# O2_PROM_ISP_A00.net
KiCad netlist of a schematic drawn in EAGLE
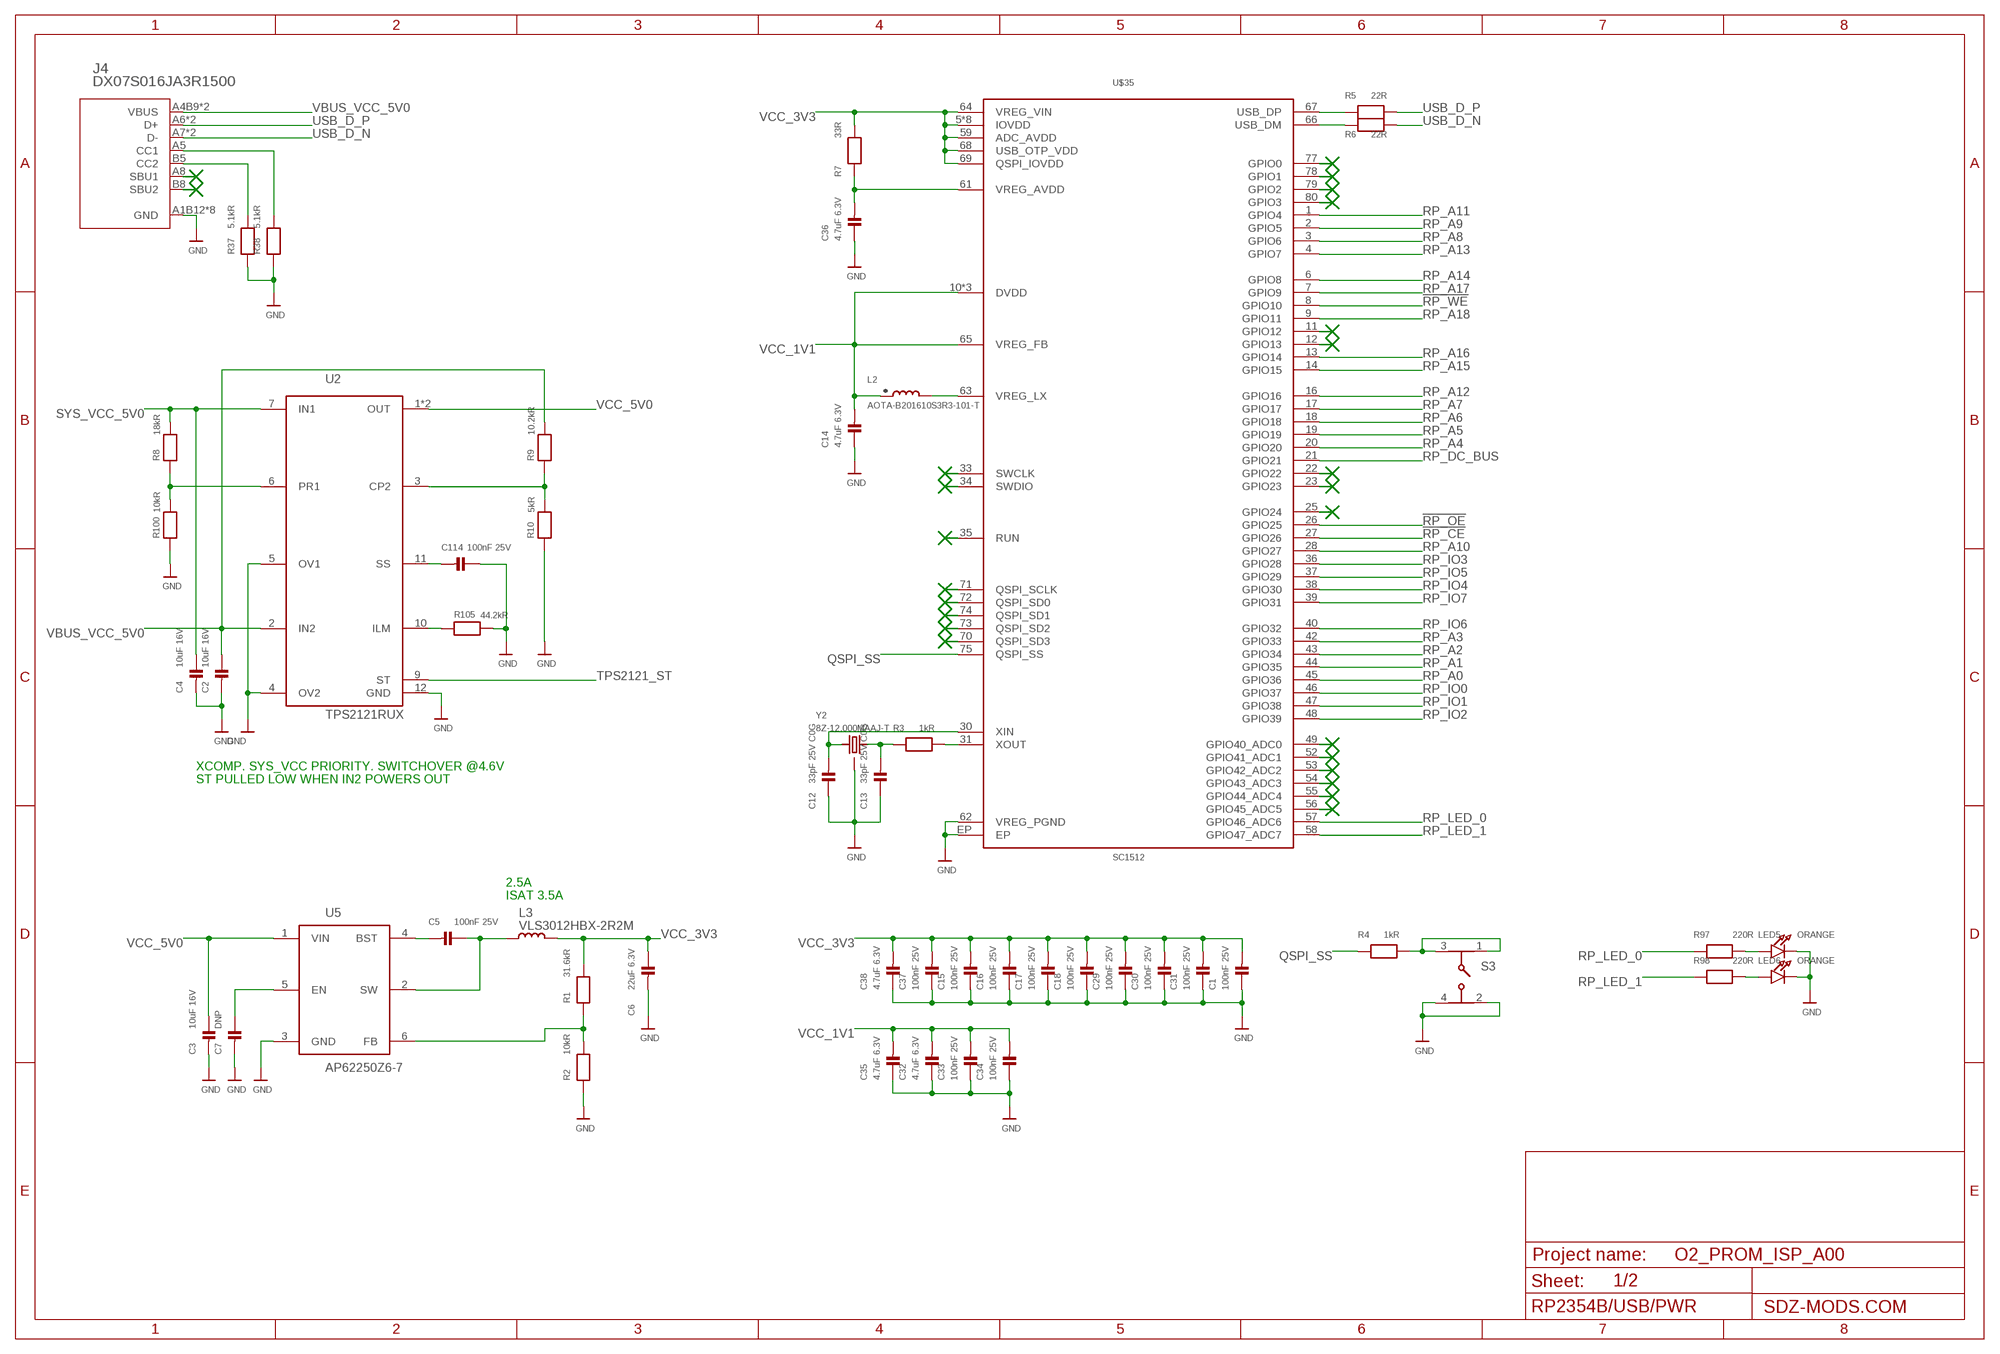
[diagram p0: schematic, sheet 1]
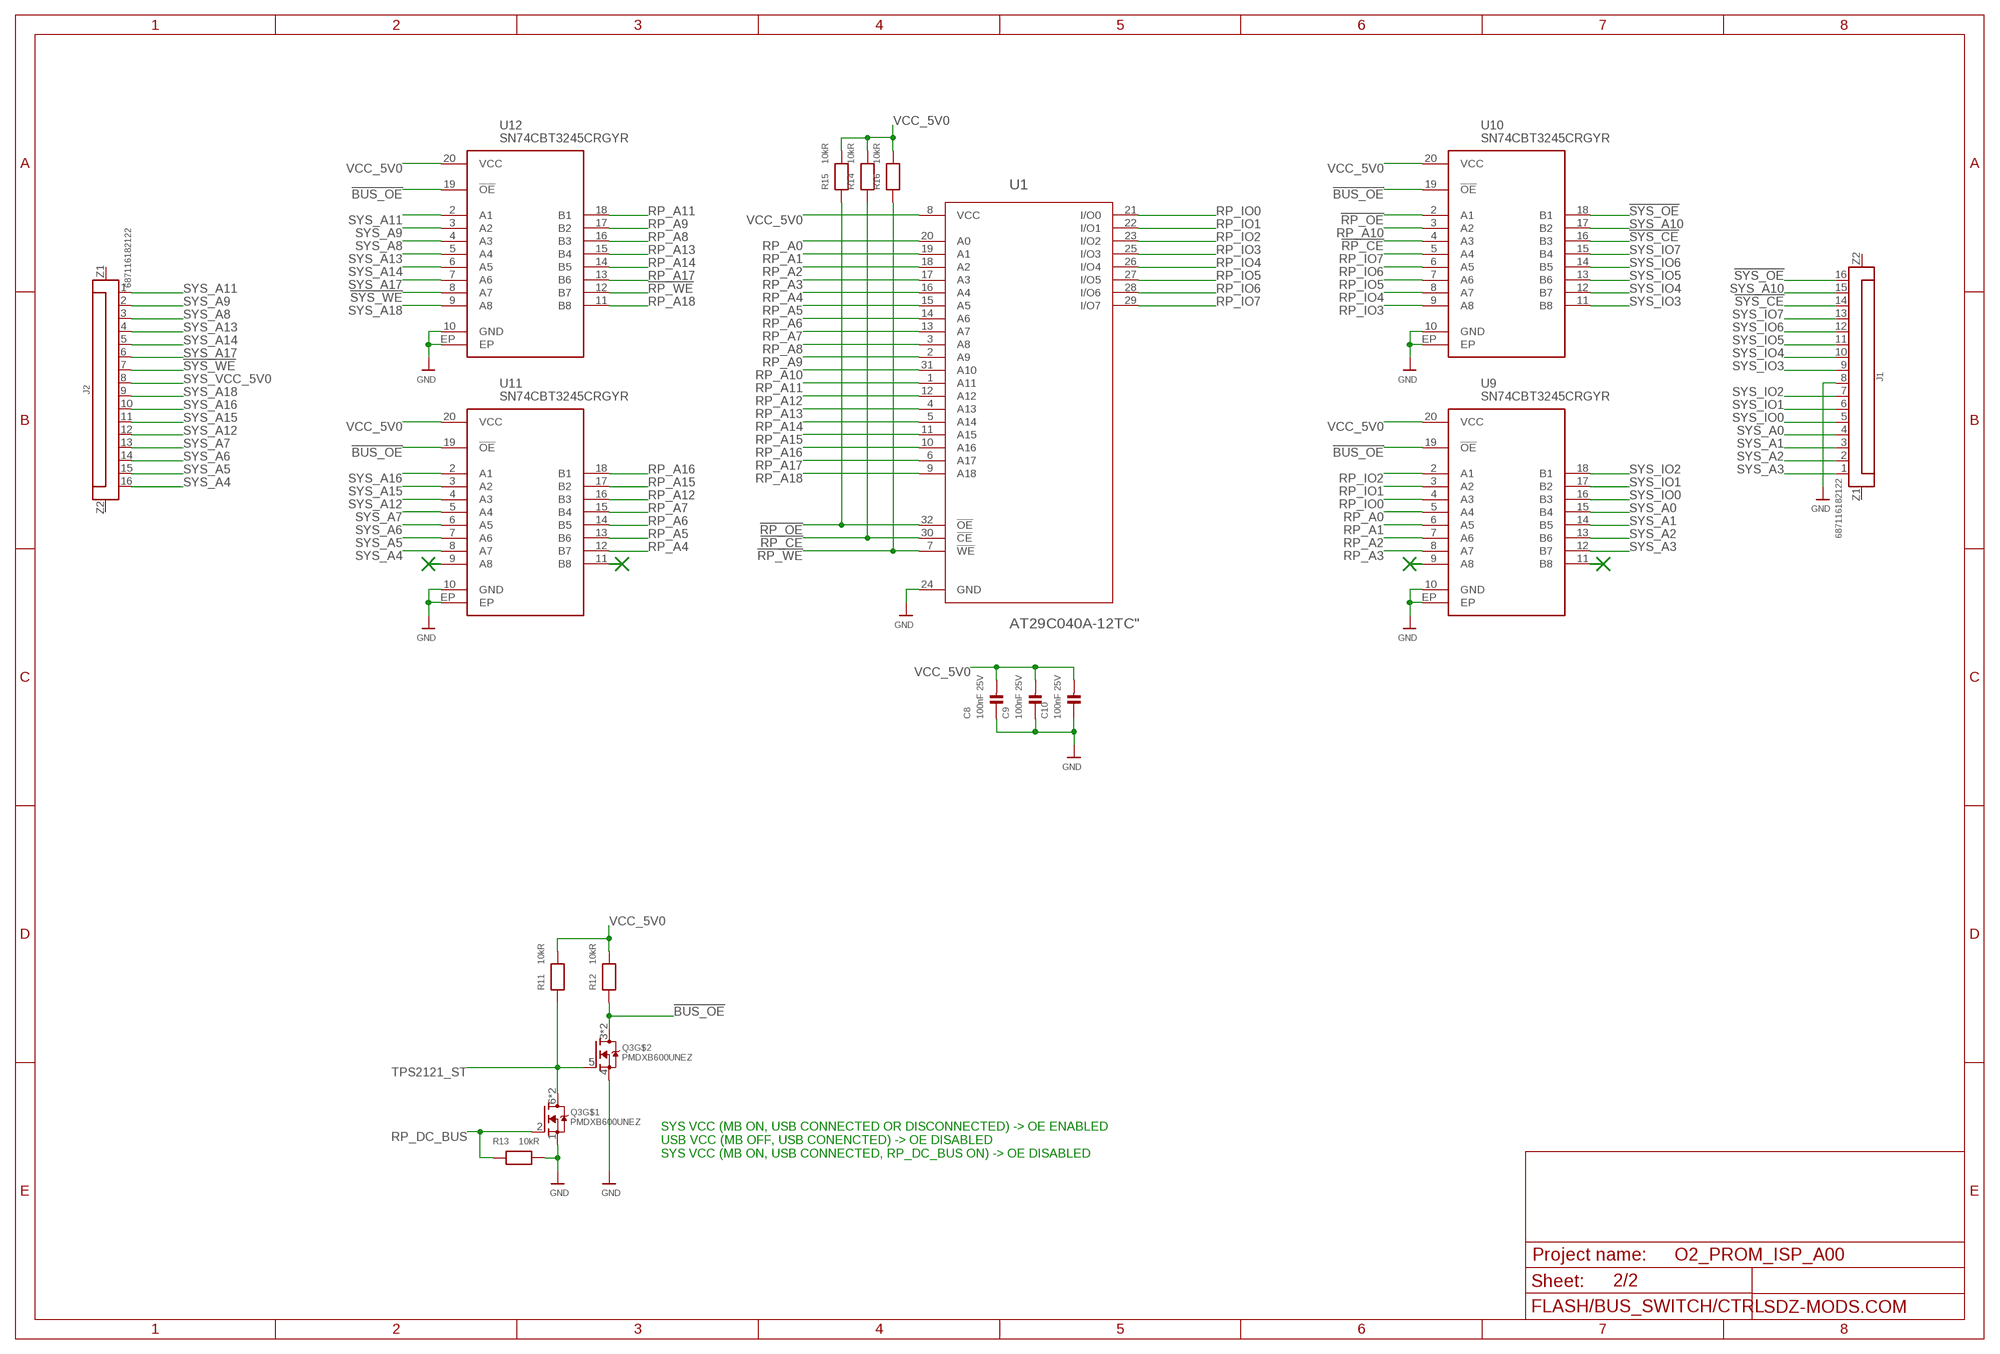
[diagram p1: schematic, sheet 2]

(export (version "E")
  (design (tool "Eeschema 10.0.6"))
  (components
    (comp (ref "C8")
      (value "100nF 25V")
      (footprint "eagle-import:0402D")
      (libsource (lib "eagle-import") (part "CAP_CERAMIC0402D"))
    )
    (comp (ref "C9")
      (value "100nF 25V")
      (footprint "eagle-import:0402D")
      (libsource (lib "eagle-import") (part "CAP_CERAMIC0402D"))
    )
    (comp (ref "C10")
      (value "100nF 25V")
      (footprint "eagle-import:0402D")
      (libsource (lib "eagle-import") (part "CAP_CERAMIC0402D"))
    )
    (comp (ref "J1")
      (value "687116182122")
      (footprint "eagle-import:687116182122")
      (libsource (lib "eagle-import") (part "6871XX182122_687116182122"))
    )
    (comp (ref "J2")
      (value "687116182122")
      (footprint "eagle-import:687116182122")
      (libsource (lib "eagle-import") (part "6871XX182122_687116182122"))
    )
    (comp (ref "Q3")
      (value "PMDXB600UNEZ")
      (footprint "eagle-import:PMDXB600UNEZ")
      (fields (field (name "MOUSER_PART_NUMBER") "771-PMDXB600UNEZ"))
      (libsource (lib "eagle-import") (part "PMDXB600UNEZ"))
    )
    (comp (ref "R11")
      (value "10kR")
      (footprint "eagle-import:0402D")
      (libsource (lib "eagle-import") (part "RESISTOR0402D"))
    )
    (comp (ref "R12")
      (value "10kR")
      (footprint "eagle-import:0402D")
      (libsource (lib "eagle-import") (part "RESISTOR0402D"))
    )
    (comp (ref "R13")
      (value "10kR")
      (footprint "eagle-import:0402D")
      (libsource (lib "eagle-import") (part "RESISTOR0402D"))
    )
    (comp (ref "R14")
      (value "10kR")
      (footprint "eagle-import:0402D")
      (libsource (lib "eagle-import") (part "RESISTOR0402D"))
    )
    (comp (ref "R15")
      (value "10kR")
      (footprint "eagle-import:0402D")
      (libsource (lib "eagle-import") (part "RESISTOR0402D"))
    )
    (comp (ref "R16")
      (value "10kR")
      (footprint "eagle-import:0402D")
      (libsource (lib "eagle-import") (part "RESISTOR0402D"))
    )
    (comp (ref "U1")
      (value "AT29C040A-12TC\"")
      (footprint "eagle-import:TSOP32_8X20")
      (libsource (lib "eagle-import") (part "AT29C040A-12TC{dblquote}"))
    )
    (comp (ref "U9")
      (value "SN74CBT3245CRGYR")
      (footprint "eagle-import:VQFN-20")
      (libsource (lib "eagle-import") (part "SN74CBT3245CRGYR"))
    )
    (comp (ref "U10")
      (value "SN74CBT3245CRGYR")
      (footprint "eagle-import:VQFN-20")
      (libsource (lib "eagle-import") (part "SN74CBT3245CRGYR"))
    )
    (comp (ref "U11")
      (value "SN74CBT3245CRGYR")
      (footprint "eagle-import:VQFN-20")
      (libsource (lib "eagle-import") (part "SN74CBT3245CRGYR"))
    )
    (comp (ref "U12")
      (value "SN74CBT3245CRGYR")
      (footprint "eagle-import:VQFN-20")
      (libsource (lib "eagle-import") (part "SN74CBT3245CRGYR"))
    )
    (comp (ref "C1")
      (value "100nF 25V")
      (footprint "eagle-import:0402D")
      (libsource (lib "eagle-import") (part "CAP_CERAMIC0402D"))
    )
    (comp (ref "C2")
      (value "10uF 16V")
      (footprint "eagle-import:0603D")
      (libsource (lib "eagle-import") (part "CAP_CERAMIC0603D"))
    )
    (comp (ref "C3")
      (value "10uF 16V")
      (footprint "eagle-import:0603D")
      (libsource (lib "eagle-import") (part "CAP_CERAMIC0603D"))
    )
    (comp (ref "C4")
      (value "10uF 16V")
      (footprint "eagle-import:0603D")
      (libsource (lib "eagle-import") (part "CAP_CERAMIC0603D"))
    )
    (comp (ref "C5")
      (value "100nF 25V")
      (footprint "eagle-import:0402D")
      (libsource (lib "eagle-import") (part "CAP_CERAMIC0402D"))
    )
    (comp (ref "C6")
      (value "22uF 6.3V")
      (footprint "eagle-import:0603D")
      (libsource (lib "eagle-import") (part "CAP_CERAMIC0603D"))
    )
    (comp (ref "C7")
      (value "DNP")
      (footprint "eagle-import:0402D")
      (libsource (lib "eagle-import") (part "CAP_CERAMIC0402D"))
    )
    (comp (ref "C12")
      (value "33pF 25V C0G")
      (footprint "eagle-import:0402D")
      (libsource (lib "eagle-import") (part "CAP_CERAMIC0402D"))
    )
    (comp (ref "C13")
      (value "33pF 25V C0G")
      (footprint "eagle-import:0402D")
      (libsource (lib "eagle-import") (part "CAP_CERAMIC0402D"))
    )
    (comp (ref "C14")
      (value "4.7uF 6.3V")
      (footprint "eagle-import:0402D")
      (libsource (lib "eagle-import") (part "CAP_CERAMIC0402D"))
    )
    (comp (ref "C15")
      (value "100nF 25V")
      (footprint "eagle-import:0402D")
      (libsource (lib "eagle-import") (part "CAP_CERAMIC0402D"))
    )
    (comp (ref "C16")
      (value "100nF 25V")
      (footprint "eagle-import:0402D")
      (libsource (lib "eagle-import") (part "CAP_CERAMIC0402D"))
    )
    (comp (ref "C17")
      (value "100nF 25V")
      (footprint "eagle-import:0402D")
      (libsource (lib "eagle-import") (part "CAP_CERAMIC0402D"))
    )
    (comp (ref "C18")
      (value "100nF 25V")
      (footprint "eagle-import:0402D")
      (libsource (lib "eagle-import") (part "CAP_CERAMIC0402D"))
    )
    (comp (ref "C29")
      (value "100nF 25V")
      (footprint "eagle-import:0402D")
      (libsource (lib "eagle-import") (part "CAP_CERAMIC0402D"))
    )
    (comp (ref "C30")
      (value "100nF 25V")
      (footprint "eagle-import:0402D")
      (libsource (lib "eagle-import") (part "CAP_CERAMIC0402D"))
    )
    (comp (ref "C31")
      (value "100nF 25V")
      (footprint "eagle-import:0402D")
      (libsource (lib "eagle-import") (part "CAP_CERAMIC0402D"))
    )
    (comp (ref "C32")
      (value "4.7uF 6.3V")
      (footprint "eagle-import:0402D")
      (libsource (lib "eagle-import") (part "CAP_CERAMIC0402D"))
    )
    (comp (ref "C33")
      (value "100nF 25V")
      (footprint "eagle-import:0402D")
      (libsource (lib "eagle-import") (part "CAP_CERAMIC0402D"))
    )
    (comp (ref "C34")
      (value "100nF 25V")
      (footprint "eagle-import:0402D")
      (libsource (lib "eagle-import") (part "CAP_CERAMIC0402D"))
    )
    (comp (ref "C35")
      (value "4.7uF 6.3V")
      (footprint "eagle-import:0402D")
      (libsource (lib "eagle-import") (part "CAP_CERAMIC0402D"))
    )
    (comp (ref "C36")
      (value "4.7uF 6.3V")
      (footprint "eagle-import:0402D")
      (libsource (lib "eagle-import") (part "CAP_CERAMIC0402D"))
    )
    (comp (ref "C37")
      (value "100nF 25V")
      (footprint "eagle-import:0402D")
      (libsource (lib "eagle-import") (part "CAP_CERAMIC0402D"))
    )
    (comp (ref "C38")
      (value "4.7uF 6.3V")
      (footprint "eagle-import:0402D")
      (libsource (lib "eagle-import") (part "CAP_CERAMIC0402D"))
    )
    (comp (ref "C114")
      (value "100nF 25V")
      (footprint "eagle-import:0402D")
      (libsource (lib "eagle-import") (part "CAP_CERAMIC0402D"))
    )
    (comp (ref "J4")
      (value "DX07S016JA3R1500")
      (footprint "eagle-import:DX07S016JA3R1500")
      (libsource (lib "eagle-import") (part "DX07S016JA3R1500"))
    )
    (comp (ref "L2")
      (value "AOTA-B201610S3R3-101-T")
      (footprint "eagle-import:0806")
      (libsource (lib "eagle-import") (part "AOTA-B201610S3R3-101-T"))
    )
    (comp (ref "L3")
      (value "VLS3012HBX-2R2M")
      (footprint "eagle-import:VLS3012")
      (fields (field (name "MOUSER_PART_NUMBER") "810-VLS3012HBX-2R2M"))
      (libsource (lib "eagle-import") (part "VLS3012HBX-2R2M"))
    )
    (comp (ref "LED5")
      (value "ORANGE")
      (footprint "eagle-import:CHIPLED_0402C")
      (libsource (lib "eagle-import") (part "LED"))
    )
    (comp (ref "LED6")
      (value "ORANGE")
      (footprint "eagle-import:CHIPLED_0402C")
      (libsource (lib "eagle-import") (part "LED"))
    )
    (comp (ref "R1")
      (value "31.6kR")
      (footprint "eagle-import:0402D")
      (libsource (lib "eagle-import") (part "RESISTOR0402D"))
    )
    (comp (ref "R2")
      (value "10kR")
      (footprint "eagle-import:0402D")
      (libsource (lib "eagle-import") (part "RESISTOR0402D"))
    )
    (comp (ref "R3")
      (value "1kR")
      (footprint "eagle-import:0402D")
      (libsource (lib "eagle-import") (part "RESISTOR0402D"))
    )
    (comp (ref "R4")
      (value "1kR")
      (footprint "eagle-import:0402D")
      (libsource (lib "eagle-import") (part "RESISTOR0402D"))
    )
    (comp (ref "R5")
      (value "22R")
      (footprint "eagle-import:0402D")
      (libsource (lib "eagle-import") (part "RESISTOR0402D"))
    )
    (comp (ref "R6")
      (value "22R")
      (footprint "eagle-import:0402D")
      (libsource (lib "eagle-import") (part "RESISTOR0402D"))
    )
    (comp (ref "R7")
      (value "33R")
      (footprint "eagle-import:0402D")
      (libsource (lib "eagle-import") (part "RESISTOR0402D"))
    )
    (comp (ref "R8")
      (value "18kR")
      (footprint "eagle-import:0402D")
      (libsource (lib "eagle-import") (part "RESISTOR0402D"))
    )
    (comp (ref "R9")
      (value "10.2kR")
      (footprint "eagle-import:0402D")
      (libsource (lib "eagle-import") (part "RESISTOR0402D"))
    )
    (comp (ref "R10")
      (value "5kR")
      (footprint "eagle-import:0402D")
      (libsource (lib "eagle-import") (part "RESISTOR0402D"))
    )
    (comp (ref "R37")
      (value "5.1kR")
      (footprint "eagle-import:0402D")
      (libsource (lib "eagle-import") (part "RESISTOR0402D"))
    )
    (comp (ref "R38")
      (value "5.1kR")
      (footprint "eagle-import:0402D")
      (libsource (lib "eagle-import") (part "RESISTOR0402D"))
    )
    (comp (ref "R97")
      (value "220R")
      (footprint "eagle-import:0402D")
      (libsource (lib "eagle-import") (part "RESISTOR0402D"))
    )
    (comp (ref "R98")
      (value "220R")
      (footprint "eagle-import:0402D")
      (libsource (lib "eagle-import") (part "RESISTOR0402D"))
    )
    (comp (ref "R100")
      (value "10kR")
      (footprint "eagle-import:0402D")
      (libsource (lib "eagle-import") (part "RESISTOR0402D"))
    )
    (comp (ref "R105")
      (value "44.2kR")
      (footprint "eagle-import:0402D")
      (libsource (lib "eagle-import") (part "RESISTOR0402D"))
    )
    (comp (ref "S3")
      (value "434353045816")
      (footprint "eagle-import:434353045816")
      (libsource (lib "eagle-import") (part "434353045816"))
    )
    (comp (ref "U$35")
      (value "SC1512")
      (footprint "eagle-import:SC1512")
      (libsource (lib "eagle-import") (part "SC1512"))
    )
    (comp (ref "U2")
      (value "TPS2121RUX")
      (footprint "eagle-import:VQFN-HR-12")
      (libsource (lib "eagle-import") (part "TPS2121RUX"))
    )
    (comp (ref "U5")
      (value "AP62250Z6-7")
      (footprint "eagle-import:SOTFL50P160X60-6N")
      (fields (field (name "MOUSER_PART_NUMBER") "621-AP62250Z6-7"))
      (libsource (lib "eagle-import") (part "AP62250Z6-7"))
    )
    (comp (ref "Y2")
      (value "8Z-12.000MAAJ-T")
      (footprint "eagle-import:TXC-8Z-25X20")
      (libsource (lib "eagle-import") (part "TXC-8Z-25X20"))
    )
  )
  (nets
    (net (code "1") (name "GND") (class "Default")
      (node (ref "C1") (pin "3") (pinfunction "P$1_3") (pintype "passive"))
      (node (ref "C10") (pin "3") (pinfunction "P$1_3") (pintype "passive"))
      (node (ref "C114") (pin "3") (pinfunction "P$1_3") (pintype "passive"))
      (node (ref "C12") (pin "3") (pinfunction "P$1_3") (pintype "passive"))
      (node (ref "C13") (pin "3") (pinfunction "P$1_3") (pintype "passive"))
      (node (ref "C14") (pin "3") (pinfunction "P$1_3") (pintype "passive"))
      (node (ref "C15") (pin "3") (pinfunction "P$1_3") (pintype "passive"))
      (node (ref "C16") (pin "3") (pinfunction "P$1_3") (pintype "passive"))
      (node (ref "C17") (pin "3") (pinfunction "P$1_3") (pintype "passive"))
      (node (ref "C18") (pin "3") (pinfunction "P$1_3") (pintype "passive"))
      (node (ref "C2") (pin "2") (pinfunction "P$2_2") (pintype "passive"))
      (node (ref "C29") (pin "3") (pinfunction "P$1_3") (pintype "passive"))
      (node (ref "C3") (pin "2") (pinfunction "P$2_2") (pintype "passive"))
      (node (ref "C30") (pin "3") (pinfunction "P$1_3") (pintype "passive"))
      (node (ref "C31") (pin "3") (pinfunction "P$1_3") (pintype "passive"))
      (node (ref "C32") (pin "3") (pinfunction "P$1_3") (pintype "passive"))
      (node (ref "C33") (pin "3") (pinfunction "P$1_3") (pintype "passive"))
      (node (ref "C34") (pin "3") (pinfunction "P$1_3") (pintype "passive"))
      (node (ref "C35") (pin "3") (pinfunction "P$1_3") (pintype "passive"))
      (node (ref "C36") (pin "3") (pinfunction "P$1_3") (pintype "passive"))
      (node (ref "C37") (pin "3") (pinfunction "P$1_3") (pintype "passive"))
      (node (ref "C38") (pin "3") (pinfunction "P$1_3") (pintype "passive"))
      (node (ref "C4") (pin "2") (pinfunction "P$2_2") (pintype "passive"))
      (node (ref "C6") (pin "2") (pinfunction "P$2_2") (pintype "passive"))
      (node (ref "C7") (pin "4") (pinfunction "P$2_4") (pintype "passive"))
      (node (ref "C8") (pin "3") (pinfunction "P$1_3") (pintype "passive"))
      (node (ref "C9") (pin "3") (pinfunction "P$1_3") (pintype "passive"))
      (node (ref "J1") (pin "8") (pinfunction "8_8") (pintype "passive"))
      (node (ref "J4") (pin "A12/B1") (pinfunction "GND_A12/B1") (pintype "bidirectional"))
      (node (ref "J4") (pin "A1B12") (pinfunction "GND_A1B12") (pintype "bidirectional"))
      (node (ref "J4") (pin "MH1") (pinfunction "GND_MH1") (pintype "bidirectional"))
      (node (ref "J4") (pin "MH2") (pinfunction "GND_MH2") (pintype "bidirectional"))
      (node (ref "J4") (pin "MH3") (pinfunction "GND_MH3") (pintype "bidirectional"))
      (node (ref "J4") (pin "MH4") (pinfunction "GND_MH4") (pintype "bidirectional"))
      (node (ref "J4") (pin "MP1") (pinfunction "GND_MP1") (pintype "bidirectional"))
      (node (ref "J4") (pin "MP2") (pinfunction "GND_MP2") (pintype "bidirectional"))
      (node (ref "LED5") (pin "4") (pinfunction "C_4") (pintype "passive"))
      (node (ref "LED6") (pin "4") (pinfunction "C_4") (pintype "passive"))
      (node (ref "Q3") (pin "1") (pinfunction "S_1") (pintype "bidirectional"))
      (node (ref "Q3") (pin "4") (pinfunction "S_4") (pintype "bidirectional"))
      (node (ref "R10") (pin "3") (pinfunction "1_3") (pintype "passive"))
      (node (ref "R100") (pin "3") (pinfunction "1_3") (pintype "passive"))
      (node (ref "R105") (pin "4") (pinfunction "2_4") (pintype "passive"))
      (node (ref "R13") (pin "3") (pinfunction "1_3") (pintype "passive"))
      (node (ref "R2") (pin "4") (pinfunction "2_4") (pintype "passive"))
      (node (ref "R37") (pin "3") (pinfunction "1_3") (pintype "passive"))
      (node (ref "R38") (pin "3") (pinfunction "1_3") (pintype "passive"))
      (node (ref "S3") (pin "2") (pinfunction "4_2") (pintype "passive"))
      (node (ref "S3") (pin "4") (pinfunction "2_4") (pintype "passive"))
      (node (ref "U$35") (pin "62") (pinfunction "VREG_PGND_62") (pintype "bidirectional"))
      (node (ref "U$35") (pin "EP") (pinfunction "EP_EP") (pintype "bidirectional"))
      (node (ref "U1") (pin "24") (pinfunction "GND_24") (pintype "passive"))
      (node (ref "U10") (pin "10") (pinfunction "GND_10") (pintype "bidirectional"))
      (node (ref "U10") (pin "EP") (pinfunction "EP_EP") (pintype "bidirectional"))
      (node (ref "U11") (pin "10") (pinfunction "GND_10") (pintype "bidirectional"))
      (node (ref "U11") (pin "EP") (pinfunction "EP_EP") (pintype "bidirectional"))
      (node (ref "U12") (pin "10") (pinfunction "GND_10") (pintype "bidirectional"))
      (node (ref "U12") (pin "EP") (pinfunction "EP_EP") (pintype "bidirectional"))
      (node (ref "U2") (pin "12") (pinfunction "GND_12") (pintype "bidirectional"))
      (node (ref "U2") (pin "4") (pinfunction "OV2_4") (pintype "bidirectional"))
      (node (ref "U2") (pin "5") (pinfunction "OV1_5") (pintype "bidirectional"))
      (node (ref "U5") (pin "3") (pinfunction "GND_3") (pintype "bidirectional"))
      (node (ref "U9") (pin "10") (pinfunction "GND_10") (pintype "bidirectional"))
      (node (ref "U9") (pin "EP") (pinfunction "EP_EP") (pintype "bidirectional"))
      (node (ref "Y2") (pin "2") (pinfunction "GND_2") (pintype "bidirectional"))
      (node (ref "Y2") (pin "4") (pinfunction "GND_4") (pintype "bidirectional"))
    )
    (net (code "2") (name "Net-(C5-P$1)") (class "Default")
      (node (ref "C5") (pin "3") (pinfunction "P$1_3") (pintype "passive"))
      (node (ref "L3") (pin "1") (pinfunction "3_1") (pintype "passive"))
      (node (ref "U5") (pin "2") (pinfunction "SW_2") (pintype "bidirectional"))
    )
    (net (code "3") (name "Net-(C5-P$2)") (class "Default")
      (node (ref "C5") (pin "4") (pinfunction "P$2_4") (pintype "passive"))
      (node (ref "U5") (pin "4") (pinfunction "BST_4") (pintype "bidirectional"))
    )
    (net (code "4") (name "Net-(C7-P$1)") (class "Default")
      (node (ref "C7") (pin "3") (pinfunction "P$1_3") (pintype "passive"))
      (node (ref "U5") (pin "5") (pinfunction "EN_5") (pintype "bidirectional"))
    )
    (net (code "5") (name "Net-(C12-P$2)") (class "Default")
      (node (ref "C12") (pin "4") (pinfunction "P$2_4") (pintype "passive"))
      (node (ref "U$35") (pin "30") (pinfunction "XIN_30") (pintype "bidirectional"))
      (node (ref "Y2") (pin "1") (pinfunction "1_1") (pintype "passive"))
    )
    (net (code "6") (name "Net-(C13-P$2)") (class "Default")
      (node (ref "C13") (pin "4") (pinfunction "P$2_4") (pintype "passive"))
      (node (ref "R3") (pin "3") (pinfunction "1_3") (pintype "passive"))
      (node (ref "Y2") (pin "3") (pinfunction "2_3") (pintype "passive"))
    )
    (net (code "7") (name "Net-(C36-P$2)") (class "Default")
      (node (ref "C36") (pin "4") (pinfunction "P$2_4") (pintype "passive"))
      (node (ref "R7") (pin "4") (pinfunction "2_4") (pintype "passive"))
      (node (ref "U$35") (pin "61") (pinfunction "VREG_AVDD_61") (pintype "bidirectional"))
    )
    (net (code "8") (name "Net-(C114-P$2)") (class "Default")
      (node (ref "C114") (pin "4") (pinfunction "P$2_4") (pintype "passive"))
      (node (ref "U2") (pin "11") (pinfunction "SS_11") (pintype "bidirectional"))
    )
    (net (code "9") (name "Net-(J4-CC1)") (class "Default")
      (node (ref "J4") (pin "A5") (pinfunction "CC1_A5") (pintype "bidirectional"))
      (node (ref "R38") (pin "4") (pinfunction "2_4") (pintype "passive"))
    )
    (net (code "10") (name "Net-(J4-CC2)") (class "Default")
      (node (ref "J4") (pin "B5") (pinfunction "CC2_B5") (pintype "bidirectional"))
      (node (ref "R37") (pin "4") (pinfunction "2_4") (pintype "passive"))
    )
    (net (code "11") (name "Net-(LED5-A)") (class "Default")
      (node (ref "LED5") (pin "3") (pinfunction "A_3") (pintype "passive"))
      (node (ref "R97") (pin "3") (pinfunction "1_3") (pintype "passive"))
    )
    (net (code "12") (name "Net-(LED6-A)") (class "Default")
      (node (ref "LED6") (pin "3") (pinfunction "A_3") (pintype "passive"))
      (node (ref "R98") (pin "3") (pinfunction "1_3") (pintype "passive"))
    )
    (net (code "13") (name "Net-(R1-2)") (class "Default")
      (node (ref "R1") (pin "4") (pinfunction "2_4") (pintype "passive"))
      (node (ref "R2") (pin "3") (pinfunction "1_3") (pintype "passive"))
      (node (ref "U5") (pin "6") (pinfunction "FB_6") (pintype "bidirectional"))
    )
    (net (code "14") (name "Net-(R3-2)") (class "Default")
      (node (ref "R3") (pin "4") (pinfunction "2_4") (pintype "passive"))
      (node (ref "U$35") (pin "31") (pinfunction "XOUT_31") (pintype "bidirectional"))
    )
    (net (code "15") (name "Net-(R4-2)") (class "Default")
      (node (ref "R4") (pin "4") (pinfunction "2_4") (pintype "passive"))
      (node (ref "S3") (pin "1") (pinfunction "3_1") (pintype "passive"))
      (node (ref "S3") (pin "3") (pinfunction "1_3") (pintype "passive"))
    )
    (net (code "16") (name "Net-(R5-1)") (class "Default")
      (node (ref "R5") (pin "3") (pinfunction "1_3") (pintype "passive"))
      (node (ref "U$35") (pin "67") (pinfunction "USB_DP_67") (pintype "bidirectional"))
    )
    (net (code "17") (name "Net-(R6-1)") (class "Default")
      (node (ref "R6") (pin "3") (pinfunction "1_3") (pintype "passive"))
      (node (ref "U$35") (pin "66") (pinfunction "USB_DM_66") (pintype "bidirectional"))
    )
    (net (code "18") (name "Net-(R10-2)") (class "Default")
      (node (ref "R10") (pin "4") (pinfunction "2_4") (pintype "passive"))
      (node (ref "R9") (pin "3") (pinfunction "1_3") (pintype "passive"))
      (node (ref "U2") (pin "3") (pinfunction "CP2_3") (pintype "bidirectional"))
    )
    (net (code "19") (name "Net-(R100-2)") (class "Default")
      (node (ref "R100") (pin "4") (pinfunction "2_4") (pintype "passive"))
      (node (ref "R8") (pin "3") (pinfunction "1_3") (pintype "passive"))
      (node (ref "U2") (pin "6") (pinfunction "PR1_6") (pintype "bidirectional"))
    )
    (net (code "20") (name "Net-(R105-1)") (class "Default")
      (node (ref "R105") (pin "3") (pinfunction "1_3") (pintype "passive"))
      (node (ref "U2") (pin "10") (pinfunction "ILM_10") (pintype "bidirectional"))
    )
    (net (code "21") (name "Net-(U$35-VREG_LX)") (class "Default")
      (node (ref "L2") (pin "2") (pinfunction "2_2") (pintype "passive"))
      (node (ref "U$35") (pin "63") (pinfunction "VREG_LX_63") (pintype "bidirectional"))
    )
    (net (code "22") (name "QSPI_SS") (class "Default")
      (node (ref "R4") (pin "3") (pinfunction "1_3") (pintype "passive"))
      (node (ref "U$35") (pin "75") (pinfunction "QSPI_SS_75") (pintype "bidirectional"))
    )
    (net (code "23") (name "RP_A0") (class "Default")
      (node (ref "U$35") (pin "45") (pinfunction "GPIO36_45") (pintype "bidirectional"))
      (node (ref "U1") (pin "20") (pinfunction "A0_20") (pintype "bidirectional"))
      (node (ref "U9") (pin "5") (pinfunction "A4_5") (pintype "bidirectional"))
    )
    (net (code "24") (name "RP_A1") (class "Default")
      (node (ref "U$35") (pin "44") (pinfunction "GPIO35_44") (pintype "bidirectional"))
      (node (ref "U1") (pin "19") (pinfunction "A1_19") (pintype "bidirectional"))
      (node (ref "U9") (pin "6") (pinfunction "A5_6") (pintype "bidirectional"))
    )
    (net (code "25") (name "RP_A2") (class "Default")
      (node (ref "U$35") (pin "43") (pinfunction "GPIO34_43") (pintype "bidirectional"))
      (node (ref "U1") (pin "18") (pinfunction "A2_18") (pintype "bidirectional"))
      (node (ref "U9") (pin "7") (pinfunction "A6_7") (pintype "bidirectional"))
    )
    (net (code "26") (name "RP_A3") (class "Default")
      (node (ref "U$35") (pin "42") (pinfunction "GPIO33_42") (pintype "bidirectional"))
      (node (ref "U1") (pin "17") (pinfunction "A3_17") (pintype "bidirectional"))
      (node (ref "U9") (pin "8") (pinfunction "A7_8") (pintype "bidirectional"))
    )
    (net (code "27") (name "RP_A4") (class "Default")
      (node (ref "U$35") (pin "20") (pinfunction "GPIO20_20") (pintype "bidirectional"))
      (node (ref "U1") (pin "16") (pinfunction "A4_16") (pintype "bidirectional"))
      (node (ref "U11") (pin "12") (pinfunction "B7_12") (pintype "bidirectional"))
    )
    (net (code "28") (name "RP_A5") (class "Default")
      (node (ref "U$35") (pin "19") (pinfunction "GPIO19_19") (pintype "bidirectional"))
      (node (ref "U1") (pin "15") (pinfunction "A5_15") (pintype "bidirectional"))
      (node (ref "U11") (pin "13") (pinfunction "B6_13") (pintype "bidirectional"))
    )
    (net (code "29") (name "RP_A6") (class "Default")
      (node (ref "U$35") (pin "18") (pinfunction "GPIO18_18") (pintype "bidirectional"))
      (node (ref "U1") (pin "14") (pinfunction "A6_14") (pintype "bidirectional"))
      (node (ref "U11") (pin "14") (pinfunction "B5_14") (pintype "bidirectional"))
    )
    (net (code "30") (name "RP_A7") (class "Default")
      (node (ref "U$35") (pin "17") (pinfunction "GPIO17_17") (pintype "bidirectional"))
      (node (ref "U1") (pin "13") (pinfunction "A7_13") (pintype "bidirectional"))
      (node (ref "U11") (pin "15") (pinfunction "B4_15") (pintype "bidirectional"))
    )
    (net (code "31") (name "RP_A8") (class "Default")
      (node (ref "U$35") (pin "3") (pinfunction "GPIO6_3") (pintype "bidirectional"))
      (node (ref "U1") (pin "3") (pinfunction "A8_3") (pintype "bidirectional"))
      (node (ref "U12") (pin "16") (pinfunction "B3_16") (pintype "bidirectional"))
    )
    (net (code "32") (name "RP_A9") (class "Default")
      (node (ref "U$35") (pin "2") (pinfunction "GPIO5_2") (pintype "bidirectional"))
      (node (ref "U1") (pin "2") (pinfunction "A9_2") (pintype "bidirectional"))
      (node (ref "U12") (pin "17") (pinfunction "B2_17") (pintype "bidirectional"))
    )
    (net (code "33") (name "RP_A10") (class "Default")
      (node (ref "U$35") (pin "28") (pinfunction "GPIO27_28") (pintype "bidirectional"))
      (node (ref "U1") (pin "31") (pinfunction "A10_31") (pintype "passive"))
      (node (ref "U10") (pin "3") (pinfunction "A2_3") (pintype "bidirectional"))
    )
    (net (code "34") (name "RP_A11") (class "Default")
      (node (ref "U$35") (pin "1") (pinfunction "GPIO4_1") (pintype "bidirectional"))
      (node (ref "U1") (pin "1") (pinfunction "A11_1") (pintype "bidirectional"))
      (node (ref "U12") (pin "18") (pinfunction "B1_18") (pintype "bidirectional"))
    )
    (net (code "35") (name "RP_A12") (class "Default")
      (node (ref "U$35") (pin "16") (pinfunction "GPIO16_16") (pintype "bidirectional"))
      (node (ref "U1") (pin "12") (pinfunction "A12_12") (pintype "bidirectional"))
      (node (ref "U11") (pin "16") (pinfunction "B3_16") (pintype "bidirectional"))
    )
    (net (code "36") (name "RP_A13") (class "Default")
      (node (ref "U$35") (pin "4") (pinfunction "GPIO7_4") (pintype "bidirectional"))
      (node (ref "U1") (pin "4") (pinfunction "A13_4") (pintype "bidirectional"))
      (node (ref "U12") (pin "15") (pinfunction "B4_15") (pintype "bidirectional"))
    )
    (net (code "37") (name "RP_A14") (class "Default")
      (node (ref "U$35") (pin "6") (pinfunction "GPIO8_6") (pintype "bidirectional"))
      (node (ref "U1") (pin "5") (pinfunction "A14_5") (pintype "bidirectional"))
      (node (ref "U12") (pin "14") (pinfunction "B5_14") (pintype "bidirectional"))
    )
    (net (code "38") (name "RP_A15") (class "Default")
      (node (ref "U$35") (pin "14") (pinfunction "GPIO15_14") (pintype "bidirectional"))
      (node (ref "U1") (pin "11") (pinfunction "A15_11") (pintype "bidirectional"))
      (node (ref "U11") (pin "17") (pinfunction "B2_17") (pintype "bidirectional"))
    )
    (net (code "39") (name "RP_A16") (class "Default")
      (node (ref "U$35") (pin "13") (pinfunction "GPIO14_13") (pintype "bidirectional"))
      (node (ref "U1") (pin "10") (pinfunction "A16_10") (pintype "bidirectional"))
      (node (ref "U11") (pin "18") (pinfunction "B1_18") (pintype "bidirectional"))
    )
    (net (code "40") (name "RP_A17") (class "Default")
      (node (ref "U$35") (pin "7") (pinfunction "GPIO9_7") (pintype "bidirectional"))
      (node (ref "U1") (pin "6") (pinfunction "A17_6") (pintype "bidirectional"))
      (node (ref "U12") (pin "13") (pinfunction "B6_13") (pintype "bidirectional"))
    )
    (net (code "41") (name "RP_A18") (class "Default")
      (node (ref "U$35") (pin "9") (pinfunction "GPIO11_9") (pintype "bidirectional"))
      (node (ref "U1") (pin "9") (pinfunction "A18_9") (pintype "bidirectional"))
      (node (ref "U12") (pin "11") (pinfunction "B8_11") (pintype "bidirectional"))
    )
    (net (code "42") (name "RP_DC_BUS") (class "Default")
      (node (ref "Q3") (pin "2") (pinfunction "G_2") (pintype "bidirectional"))
      (node (ref "R13") (pin "4") (pinfunction "2_4") (pintype "passive"))
      (node (ref "U$35") (pin "21") (pinfunction "GPIO21_21") (pintype "bidirectional"))
    )
    (net (code "43") (name "RP_IO0") (class "Default")
      (node (ref "U$35") (pin "46") (pinfunction "GPIO37_46") (pintype "bidirectional"))
      (node (ref "U1") (pin "21") (pinfunction "I/O0_21") (pintype "bidirectional"))
      (node (ref "U9") (pin "4") (pinfunction "A3_4") (pintype "bidirectional"))
    )
    (net (code "44") (name "RP_IO1") (class "Default")
      (node (ref "U$35") (pin "47") (pinfunction "GPIO38_47") (pintype "bidirectional"))
      (node (ref "U1") (pin "22") (pinfunction "I/O1_22") (pintype "bidirectional"))
      (node (ref "U9") (pin "3") (pinfunction "A2_3") (pintype "bidirectional"))
    )
    (net (code "45") (name "RP_IO2") (class "Default")
      (node (ref "U$35") (pin "48") (pinfunction "GPIO39_48") (pintype "bidirectional"))
      (node (ref "U1") (pin "23") (pinfunction "I/O2_23") (pintype "bidirectional"))
      (node (ref "U9") (pin "2") (pinfunction "A1_2") (pintype "bidirectional"))
    )
    (net (code "46") (name "RP_IO3") (class "Default")
      (node (ref "U$35") (pin "36") (pinfunction "GPIO28_36") (pintype "bidirectional"))
      (node (ref "U1") (pin "25") (pinfunction "I/O3_25") (pintype "bidirectional"))
      (node (ref "U10") (pin "9") (pinfunction "A8_9") (pintype "bidirectional"))
    )
    (net (code "47") (name "RP_IO4") (class "Default")
      (node (ref "U$35") (pin "38") (pinfunction "GPIO30_38") (pintype "bidirectional"))
      (node (ref "U1") (pin "26") (pinfunction "I/O4_26") (pintype "bidirectional"))
      (node (ref "U10") (pin "8") (pinfunction "A7_8") (pintype "bidirectional"))
    )
    (net (code "48") (name "RP_IO5") (class "Default")
      (node (ref "U$35") (pin "37") (pinfunction "GPIO29_37") (pintype "bidirectional"))
      (node (ref "U1") (pin "27") (pinfunction "I/O5_27") (pintype "bidirectional"))
      (node (ref "U10") (pin "7") (pinfunction "A6_7") (pintype "bidirectional"))
    )
    (net (code "49") (name "RP_IO6") (class "Default")
      (node (ref "U$35") (pin "40") (pinfunction "GPIO32_40") (pintype "bidirectional"))
      (node (ref "U1") (pin "28") (pinfunction "I/O6_28") (pintype "bidirectional"))
      (node (ref "U10") (pin "6") (pinfunction "A5_6") (pintype "bidirectional"))
    )
    (net (code "50") (name "RP_IO7") (class "Default")
      (node (ref "U$35") (pin "39") (pinfunction "GPIO31_39") (pintype "bidirectional"))
      (node (ref "U1") (pin "29") (pinfunction "I/O7_29") (pintype "passive"))
      (node (ref "U10") (pin "5") (pinfunction "A4_5") (pintype "bidirectional"))
    )
    (net (code "51") (name "RP_LED_0") (class "Default")
      (node (ref "R97") (pin "4") (pinfunction "2_4") (pintype "passive"))
      (node (ref "U$35") (pin "57") (pinfunction "GPIO46_ADC6_57") (pintype "bidirectional"))
    )
    (net (code "52") (name "RP_LED_1") (class "Default")
      (node (ref "R98") (pin "4") (pinfunction "2_4") (pintype "passive"))
      (node (ref "U$35") (pin "58") (pinfunction "GPIO47_ADC7_58") (pintype "bidirectional"))
    )
    (net (code "53") (name "SYS_A0") (class "Default")
      (node (ref "J1") (pin "4") (pinfunction "4_4") (pintype "passive"))
      (node (ref "U9") (pin "15") (pinfunction "B4_15") (pintype "bidirectional"))
    )
    (net (code "54") (name "SYS_A1") (class "Default")
      (node (ref "J1") (pin "3") (pinfunction "3_3") (pintype "passive"))
      (node (ref "U9") (pin "14") (pinfunction "B5_14") (pintype "bidirectional"))
    )
    (net (code "55") (name "SYS_A2") (class "Default")
      (node (ref "J1") (pin "2") (pinfunction "2_2") (pintype "passive"))
      (node (ref "U9") (pin "13") (pinfunction "B6_13") (pintype "bidirectional"))
    )
    (net (code "56") (name "SYS_A3") (class "Default")
      (node (ref "J1") (pin "1") (pinfunction "1_1") (pintype "passive"))
      (node (ref "U9") (pin "12") (pinfunction "B7_12") (pintype "bidirectional"))
    )
    (net (code "57") (name "SYS_A4") (class "Default")
      (node (ref "J2") (pin "16") (pinfunction "16_16") (pintype "passive"))
      (node (ref "U11") (pin "8") (pinfunction "A7_8") (pintype "bidirectional"))
    )
    (net (code "58") (name "SYS_A5") (class "Default")
      (node (ref "J2") (pin "15") (pinfunction "15_15") (pintype "passive"))
      (node (ref "U11") (pin "7") (pinfunction "A6_7") (pintype "bidirectional"))
    )
    (net (code "59") (name "SYS_A6") (class "Default")
      (node (ref "J2") (pin "14") (pinfunction "14_14") (pintype "passive"))
      (node (ref "U11") (pin "6") (pinfunction "A5_6") (pintype "bidirectional"))
    )
    (net (code "60") (name "SYS_A7") (class "Default")
      (node (ref "J2") (pin "13") (pinfunction "13_13") (pintype "passive"))
      (node (ref "U11") (pin "5") (pinfunction "A4_5") (pintype "bidirectional"))
    )
    (net (code "61") (name "SYS_A8") (class "Default")
      (node (ref "J2") (pin "3") (pinfunction "3_3") (pintype "passive"))
      (node (ref "U12") (pin "4") (pinfunction "A3_4") (pintype "bidirectional"))
    )
    (net (code "62") (name "SYS_A9") (class "Default")
      (node (ref "J2") (pin "2") (pinfunction "2_2") (pintype "passive"))
      (node (ref "U12") (pin "3") (pinfunction "A2_3") (pintype "bidirectional"))
    )
    (net (code "63") (name "SYS_A10") (class "Default")
      (node (ref "J1") (pin "15") (pinfunction "15_15") (pintype "passive"))
      (node (ref "U10") (pin "17") (pinfunction "B2_17") (pintype "bidirectional"))
    )
    (net (code "64") (name "SYS_A11") (class "Default")
      (node (ref "J2") (pin "1") (pinfunction "1_1") (pintype "passive"))
      (node (ref "U12") (pin "2") (pinfunction "A1_2") (pintype "bidirectional"))
    )
    (net (code "65") (name "SYS_A12") (class "Default")
      (node (ref "J2") (pin "12") (pinfunction "12_12") (pintype "passive"))
      (node (ref "U11") (pin "4") (pinfunction "A3_4") (pintype "bidirectional"))
    )
    (net (code "66") (name "SYS_A13") (class "Default")
      (node (ref "J2") (pin "4") (pinfunction "4_4") (pintype "passive"))
      (node (ref "U12") (pin "5") (pinfunction "A4_5") (pintype "bidirectional"))
    )
    (net (code "67") (name "SYS_A14") (class "Default")
      (node (ref "J2") (pin "5") (pinfunction "5_5") (pintype "passive"))
      (node (ref "U12") (pin "6") (pinfunction "A5_6") (pintype "bidirectional"))
    )
    (net (code "68") (name "SYS_A15") (class "Default")
      (node (ref "J2") (pin "11") (pinfunction "11_11") (pintype "passive"))
      (node (ref "U11") (pin "3") (pinfunction "A2_3") (pintype "bidirectional"))
    )
    (net (code "69") (name "SYS_A16") (class "Default")
      (node (ref "J2") (pin "10") (pinfunction "10_10") (pintype "passive"))
      (node (ref "U11") (pin "2") (pinfunction "A1_2") (pintype "bidirectional"))
    )
    (net (code "70") (name "SYS_A17") (class "Default")
      (node (ref "J2") (pin "6") (pinfunction "6_6") (pintype "passive"))
      (node (ref "U12") (pin "7") (pinfunction "A6_7") (pintype "bidirectional"))
    )
    (net (code "71") (name "SYS_A18") (class "Default")
      (node (ref "J2") (pin "9") (pinfunction "9_9") (pintype "passive"))
      (node (ref "U12") (pin "9") (pinfunction "A8_9") (pintype "bidirectional"))
    )
    (net (code "72") (name "SYS_IO0") (class "Default")
      (node (ref "J1") (pin "5") (pinfunction "5_5") (pintype "passive"))
      (node (ref "U9") (pin "16") (pinfunction "B3_16") (pintype "bidirectional"))
    )
    (net (code "73") (name "SYS_IO1") (class "Default")
      (node (ref "J1") (pin "6") (pinfunction "6_6") (pintype "passive"))
      (node (ref "U9") (pin "17") (pinfunction "B2_17") (pintype "bidirectional"))
    )
    (net (code "74") (name "SYS_IO2") (class "Default")
      (node (ref "J1") (pin "7") (pinfunction "7_7") (pintype "passive"))
      (node (ref "U9") (pin "18") (pinfunction "B1_18") (pintype "bidirectional"))
    )
    (net (code "75") (name "SYS_IO3") (class "Default")
      (node (ref "J1") (pin "9") (pinfunction "9_9") (pintype "passive"))
      (node (ref "U10") (pin "11") (pinfunction "B8_11") (pintype "bidirectional"))
    )
    (net (code "76") (name "SYS_IO4") (class "Default")
      (node (ref "J1") (pin "10") (pinfunction "10_10") (pintype "passive"))
      (node (ref "U10") (pin "12") (pinfunction "B7_12") (pintype "bidirectional"))
    )
    (net (code "77") (name "SYS_IO5") (class "Default")
      (node (ref "J1") (pin "11") (pinfunction "11_11") (pintype "passive"))
      (node (ref "U10") (pin "13") (pinfunction "B6_13") (pintype "bidirectional"))
    )
    (net (code "78") (name "SYS_IO6") (class "Default")
      (node (ref "J1") (pin "12") (pinfunction "12_12") (pintype "passive"))
      (node (ref "U10") (pin "14") (pinfunction "B5_14") (pintype "bidirectional"))
    )
    (net (code "79") (name "SYS_IO7") (class "Default")
      (node (ref "J1") (pin "13") (pinfunction "13_13") (pintype "passive"))
      (node (ref "U10") (pin "15") (pinfunction "B4_15") (pintype "bidirectional"))
    )
    (net (code "80") (name "SYS_VCC_5V0") (class "Default")
      (node (ref "C4") (pin "1") (pinfunction "P$1_1") (pintype "passive"))
      (node (ref "J2") (pin "8") (pinfunction "8_8") (pintype "passive"))
      (node (ref "R8") (pin "4") (pinfunction "2_4") (pintype "passive"))
      (node (ref "U2") (pin "7") (pinfunction "IN1_7") (pintype "bidirectional"))
    )
    (net (code "81") (name "TPS2121_ST") (class "Default")
      (node (ref "Q3") (pin "5") (pinfunction "G_5") (pintype "bidirectional"))
      (node (ref "Q3") (pin "6") (pinfunction "D_6") (pintype "bidirectional"))
      (node (ref "Q3") (pin "7") (pinfunction "D_7") (pintype "bidirectional"))
      (node (ref "R11") (pin "4") (pinfunction "2_4") (pintype "passive"))
      (node (ref "U2") (pin "9") (pinfunction "ST_9") (pintype "bidirectional"))
    )
    (net (code "82") (name "USB_D_N") (class "Default")
      (node (ref "J4") (pin "A7") (pinfunction "D-_A7") (pintype "bidirectional"))
      (node (ref "J4") (pin "B7") (pinfunction "D-_B7") (pintype "bidirectional"))
      (node (ref "R6") (pin "4") (pinfunction "2_4") (pintype "passive"))
    )
    (net (code "83") (name "USB_D_P") (class "Default")
      (node (ref "J4") (pin "A6") (pinfunction "D+_A6") (pintype "bidirectional"))
      (node (ref "J4") (pin "B6") (pinfunction "D+_B6") (pintype "bidirectional"))
      (node (ref "R5") (pin "4") (pinfunction "2_4") (pintype "passive"))
    )
    (net (code "84") (name "VBUS_VCC_5V0") (class "Default")
      (node (ref "C2") (pin "1") (pinfunction "P$1_1") (pintype "passive"))
      (node (ref "J4") (pin "A4B9") (pinfunction "VBUS_A4B9") (pintype "bidirectional"))
      (node (ref "J4") (pin "B4A9") (pinfunction "VBUS_B4A9") (pintype "bidirectional"))
      (node (ref "R9") (pin "4") (pinfunction "2_4") (pintype "passive"))
      (node (ref "U2") (pin "2") (pinfunction "IN2_2") (pintype "bidirectional"))
    )
    (net (code "85") (name "VCC_1V1") (class "Default")
      (node (ref "C14") (pin "4") (pinfunction "P$2_4") (pintype "passive"))
      (node (ref "C32") (pin "4") (pinfunction "P$2_4") (pintype "passive"))
      (node (ref "C33") (pin "4") (pinfunction "P$2_4") (pintype "passive"))
      (node (ref "C34") (pin "4") (pinfunction "P$2_4") (pintype "passive"))
      (node (ref "C35") (pin "4") (pinfunction "P$2_4") (pintype "passive"))
      (node (ref "L2") (pin "1") (pinfunction "1_1") (pintype "passive"))
      (node (ref "U$35") (pin "10") (pinfunction "DVDD_10") (pintype "bidirectional"))
      (node (ref "U$35") (pin "32") (pinfunction "DVDD_32") (pintype "bidirectional"))
      (node (ref "U$35") (pin "51") (pinfunction "DVDD_51") (pintype "bidirectional"))
      (node (ref "U$35") (pin "65") (pinfunction "VREG_FB_65") (pintype "bidirectional"))
    )
    (net (code "86") (name "VCC_3V3") (class "Default")
      (node (ref "C1") (pin "4") (pinfunction "P$2_4") (pintype "passive"))
      (node (ref "C15") (pin "4") (pinfunction "P$2_4") (pintype "passive"))
      (node (ref "C16") (pin "4") (pinfunction "P$2_4") (pintype "passive"))
      (node (ref "C17") (pin "4") (pinfunction "P$2_4") (pintype "passive"))
      (node (ref "C18") (pin "4") (pinfunction "P$2_4") (pintype "passive"))
      (node (ref "C29") (pin "4") (pinfunction "P$2_4") (pintype "passive"))
      (node (ref "C30") (pin "4") (pinfunction "P$2_4") (pintype "passive"))
      (node (ref "C31") (pin "4") (pinfunction "P$2_4") (pintype "passive"))
      (node (ref "C37") (pin "4") (pinfunction "P$2_4") (pintype "passive"))
      (node (ref "C38") (pin "4") (pinfunction "P$2_4") (pintype "passive"))
      (node (ref "C6") (pin "1") (pinfunction "P$1_1") (pintype "passive"))
      (node (ref "L3") (pin "2") (pinfunction "4_2") (pintype "passive"))
      (node (ref "R1") (pin "3") (pinfunction "1_3") (pintype "passive"))
      (node (ref "R7") (pin "3") (pinfunction "1_3") (pintype "passive"))
      (node (ref "U$35") (pin "15") (pinfunction "IOVDD_15") (pintype "bidirectional"))
      (node (ref "U$35") (pin "24") (pinfunction "IOVDD_24") (pintype "bidirectional"))
      (node (ref "U$35") (pin "29") (pinfunction "IOVDD_29") (pintype "bidirectional"))
      (node (ref "U$35") (pin "41") (pinfunction "IOVDD_41") (pintype "bidirectional"))
      (node (ref "U$35") (pin "5") (pinfunction "IOVDD_5") (pintype "bidirectional"))
      (node (ref "U$35") (pin "50") (pinfunction "IOVDD_50") (pintype "bidirectional"))
      (node (ref "U$35") (pin "59") (pinfunction "ADC_AVDD_59") (pintype "bidirectional"))
      (node (ref "U$35") (pin "60") (pinfunction "IOVDD_60") (pintype "bidirectional"))
      (node (ref "U$35") (pin "64") (pinfunction "VREG_VIN_64") (pintype "bidirectional"))
      (node (ref "U$35") (pin "68") (pinfunction "USB_OTP_VDD_68") (pintype "bidirectional"))
      (node (ref "U$35") (pin "69") (pinfunction "QSPI_IOVDD_69") (pintype "bidirectional"))
      (node (ref "U$35") (pin "76") (pinfunction "IOVDD_76") (pintype "bidirectional"))
    )
    (net (code "87") (name "VCC_5V0") (class "Default")
      (node (ref "C10") (pin "4") (pinfunction "P$2_4") (pintype "passive"))
      (node (ref "C3") (pin "1") (pinfunction "P$1_1") (pintype "passive"))
      (node (ref "C8") (pin "4") (pinfunction "P$2_4") (pintype "passive"))
      (node (ref "C9") (pin "4") (pinfunction "P$2_4") (pintype "passive"))
      (node (ref "R11") (pin "3") (pinfunction "1_3") (pintype "passive"))
      (node (ref "R12") (pin "3") (pinfunction "1_3") (pintype "passive"))
      (node (ref "R14") (pin "3") (pinfunction "1_3") (pintype "passive"))
      (node (ref "R15") (pin "3") (pinfunction "1_3") (pintype "passive"))
      (node (ref "R16") (pin "3") (pinfunction "1_3") (pintype "passive"))
      (node (ref "U1") (pin "8") (pinfunction "VCC_8") (pintype "passive"))
      (node (ref "U10") (pin "20") (pinfunction "VCC_20") (pintype "bidirectional"))
      (node (ref "U11") (pin "20") (pinfunction "VCC_20") (pintype "bidirectional"))
      (node (ref "U12") (pin "20") (pinfunction "VCC_20") (pintype "bidirectional"))
      (node (ref "U2") (pin "1") (pinfunction "OUT_1") (pintype "bidirectional"))
      (node (ref "U2") (pin "8") (pinfunction "OUT_8") (pintype "bidirectional"))
      (node (ref "U5") (pin "1") (pinfunction "VIN_1") (pintype "bidirectional"))
      (node (ref "U9") (pin "20") (pinfunction "VCC_20") (pintype "bidirectional"))
    )
    (net (code "88") (name "unconnected-(J1-PadZ1)") (class "Default")
      (node (ref "J1") (pin "Z1") (pinfunction "Z1_Z1") (pintype "passive"))
    )
    (net (code "89") (name "unconnected-(J1-PadZ2)") (class "Default")
      (node (ref "J1") (pin "Z2") (pinfunction "Z2_Z2") (pintype "passive"))
    )
    (net (code "90") (name "unconnected-(J2-PadZ1)") (class "Default")
      (node (ref "J2") (pin "Z1") (pinfunction "Z1_Z1") (pintype "passive"))
    )
    (net (code "91") (name "unconnected-(J2-PadZ2)") (class "Default")
      (node (ref "J2") (pin "Z2") (pinfunction "Z2_Z2") (pintype "passive"))
    )
    (net (code "92") (name "unconnected-(J4-SBU1-PadA8)") (class "Default")
      (node (ref "J4") (pin "A8") (pinfunction "SBU1_A8") (pintype "bidirectional"))
    )
    (net (code "93") (name "unconnected-(J4-SBU2-PadB8)") (class "Default")
      (node (ref "J4") (pin "B8") (pinfunction "SBU2_B8") (pintype "bidirectional"))
    )
    (net (code "94") (name "unconnected-(U$35-GPIO0-Pad77)") (class "Default")
      (node (ref "U$35") (pin "77") (pinfunction "GPIO0_77") (pintype "bidirectional"))
    )
    (net (code "95") (name "unconnected-(U$35-GPIO1-Pad78)") (class "Default")
      (node (ref "U$35") (pin "78") (pinfunction "GPIO1_78") (pintype "bidirectional"))
    )
    (net (code "96") (name "unconnected-(U$35-GPIO2-Pad79)") (class "Default")
      (node (ref "U$35") (pin "79") (pinfunction "GPIO2_79") (pintype "bidirectional"))
    )
    (net (code "97") (name "unconnected-(U$35-GPIO3-Pad80)") (class "Default")
      (node (ref "U$35") (pin "80") (pinfunction "GPIO3_80") (pintype "bidirectional"))
    )
    (net (code "98") (name "unconnected-(U$35-GPIO12-Pad11)") (class "Default")
      (node (ref "U$35") (pin "11") (pinfunction "GPIO12_11") (pintype "bidirectional"))
    )
    (net (code "99") (name "unconnected-(U$35-GPIO13-Pad12)") (class "Default")
      (node (ref "U$35") (pin "12") (pinfunction "GPIO13_12") (pintype "bidirectional"))
    )
    (net (code "100") (name "unconnected-(U$35-GPIO22-Pad22)") (class "Default")
      (node (ref "U$35") (pin "22") (pinfunction "GPIO22_22") (pintype "bidirectional"))
    )
    (net (code "101") (name "unconnected-(U$35-GPIO23-Pad23)") (class "Default")
      (node (ref "U$35") (pin "23") (pinfunction "GPIO23_23") (pintype "bidirectional"))
    )
    (net (code "102") (name "unconnected-(U$35-GPIO24-Pad25)") (class "Default")
      (node (ref "U$35") (pin "25") (pinfunction "GPIO24_25") (pintype "bidirectional"))
    )
    (net (code "103") (name "unconnected-(U$35-GPIO40_ADC0-Pad49)") (class "Default")
      (node (ref "U$35") (pin "49") (pinfunction "GPIO40_ADC0_49") (pintype "bidirectional"))
    )
    (net (code "104") (name "unconnected-(U$35-GPIO41_ADC1-Pad52)") (class "Default")
      (node (ref "U$35") (pin "52") (pinfunction "GPIO41_ADC1_52") (pintype "bidirectional"))
    )
    (net (code "105") (name "unconnected-(U$35-GPIO42_ADC2-Pad53)") (class "Default")
      (node (ref "U$35") (pin "53") (pinfunction "GPIO42_ADC2_53") (pintype "bidirectional"))
    )
    (net (code "106") (name "unconnected-(U$35-GPIO43_ADC3-Pad54)") (class "Default")
      (node (ref "U$35") (pin "54") (pinfunction "GPIO43_ADC3_54") (pintype "bidirectional"))
    )
    (net (code "107") (name "unconnected-(U$35-GPIO44_ADC4-Pad55)") (class "Default")
      (node (ref "U$35") (pin "55") (pinfunction "GPIO44_ADC4_55") (pintype "bidirectional"))
    )
    (net (code "108") (name "unconnected-(U$35-GPIO45_ADC5-Pad56)") (class "Default")
      (node (ref "U$35") (pin "56") (pinfunction "GPIO45_ADC5_56") (pintype "bidirectional"))
    )
    (net (code "109") (name "unconnected-(U$35-QSPI_SCLK-Pad71)") (class "Default")
      (node (ref "U$35") (pin "71") (pinfunction "QSPI_SCLK_71") (pintype "bidirectional"))
    )
    (net (code "110") (name "unconnected-(U$35-QSPI_SD0-Pad72)") (class "Default")
      (node (ref "U$35") (pin "72") (pinfunction "QSPI_SD0_72") (pintype "bidirectional"))
    )
    (net (code "111") (name "unconnected-(U$35-QSPI_SD1-Pad74)") (class "Default")
      (node (ref "U$35") (pin "74") (pinfunction "QSPI_SD1_74") (pintype "bidirectional"))
    )
    (net (code "112") (name "unconnected-(U$35-QSPI_SD2-Pad73)") (class "Default")
      (node (ref "U$35") (pin "73") (pinfunction "QSPI_SD2_73") (pintype "bidirectional"))
    )
    (net (code "113") (name "unconnected-(U$35-QSPI_SD3-Pad70)") (class "Default")
      (node (ref "U$35") (pin "70") (pinfunction "QSPI_SD3_70") (pintype "bidirectional"))
    )
    (net (code "114") (name "unconnected-(U$35-RUN-Pad35)") (class "Default")
      (node (ref "U$35") (pin "35") (pinfunction "RUN_35") (pintype "bidirectional"))
    )
    (net (code "115") (name "unconnected-(U$35-SWCLK-Pad33)") (class "Default")
      (node (ref "U$35") (pin "33") (pinfunction "SWCLK_33") (pintype "bidirectional"))
    )
    (net (code "116") (name "unconnected-(U$35-SWDIO-Pad34)") (class "Default")
      (node (ref "U$35") (pin "34") (pinfunction "SWDIO_34") (pintype "bidirectional"))
    )
    (net (code "117") (name "unconnected-(U9-A8-Pad9)") (class "Default")
      (node (ref "U9") (pin "9") (pinfunction "A8_9") (pintype "bidirectional"))
    )
    (net (code "118") (name "unconnected-(U9-B8-Pad11)") (class "Default")
      (node (ref "U9") (pin "11") (pinfunction "B8_11") (pintype "bidirectional"))
    )
    (net (code "119") (name "unconnected-(U11-A8-Pad9)") (class "Default")
      (node (ref "U11") (pin "9") (pinfunction "A8_9") (pintype "bidirectional"))
    )
    (net (code "120") (name "unconnected-(U11-B8-Pad11)") (class "Default")
      (node (ref "U11") (pin "11") (pinfunction "B8_11") (pintype "bidirectional"))
    )
    (net (code "121") (name "~{BUS_OE}") (class "Default")
      (node (ref "Q3") (pin "3") (pinfunction "D_3") (pintype "bidirectional"))
      (node (ref "Q3") (pin "8") (pinfunction "D_8") (pintype "bidirectional"))
      (node (ref "R12") (pin "4") (pinfunction "2_4") (pintype "passive"))
      (node (ref "U10") (pin "19") (pinfunction "~{OE}_19") (pintype "bidirectional"))
      (node (ref "U11") (pin "19") (pinfunction "~{OE}_19") (pintype "bidirectional"))
      (node (ref "U12") (pin "19") (pinfunction "~{OE}_19") (pintype "bidirectional"))
      (node (ref "U9") (pin "19") (pinfunction "~{OE}_19") (pintype "bidirectional"))
    )
    (net (code "122") (name "~{RP_CE}") (class "Default")
      (node (ref "R14") (pin "4") (pinfunction "2_4") (pintype "passive"))
      (node (ref "U$35") (pin "27") (pinfunction "GPIO26_27") (pintype "bidirectional"))
      (node (ref "U1") (pin "30") (pinfunction "~{CE}_30") (pintype "passive"))
      (node (ref "U10") (pin "4") (pinfunction "A3_4") (pintype "bidirectional"))
    )
    (net (code "123") (name "~{RP_OE}") (class "Default")
      (node (ref "R15") (pin "4") (pinfunction "2_4") (pintype "passive"))
      (node (ref "U$35") (pin "26") (pinfunction "GPIO25_26") (pintype "bidirectional"))
      (node (ref "U1") (pin "32") (pinfunction "~{OE}_32") (pintype "passive"))
      (node (ref "U10") (pin "2") (pinfunction "A1_2") (pintype "bidirectional"))
    )
    (net (code "124") (name "~{RP_WE}") (class "Default")
      (node (ref "R16") (pin "4") (pinfunction "2_4") (pintype "passive"))
      (node (ref "U$35") (pin "8") (pinfunction "GPIO10_8") (pintype "bidirectional"))
      (node (ref "U1") (pin "7") (pinfunction "~{WE}_7") (pintype "passive"))
      (node (ref "U12") (pin "12") (pinfunction "B7_12") (pintype "bidirectional"))
    )
    (net (code "125") (name "~{SYS_CE}") (class "Default")
      (node (ref "J1") (pin "14") (pinfunction "14_14") (pintype "passive"))
      (node (ref "U10") (pin "16") (pinfunction "B3_16") (pintype "bidirectional"))
    )
    (net (code "126") (name "~{SYS_OE}") (class "Default")
      (node (ref "J1") (pin "16") (pinfunction "16_16") (pintype "passive"))
      (node (ref "U10") (pin "18") (pinfunction "B1_18") (pintype "bidirectional"))
    )
    (net (code "127") (name "~{SYS_WE}") (class "Default")
      (node (ref "J2") (pin "7") (pinfunction "7_7") (pintype "passive"))
      (node (ref "U12") (pin "8") (pinfunction "A7_8") (pintype "bidirectional"))
    )
  )
)
